# USB.net
KiCad netlist of a schematic drawn in Altium Designer
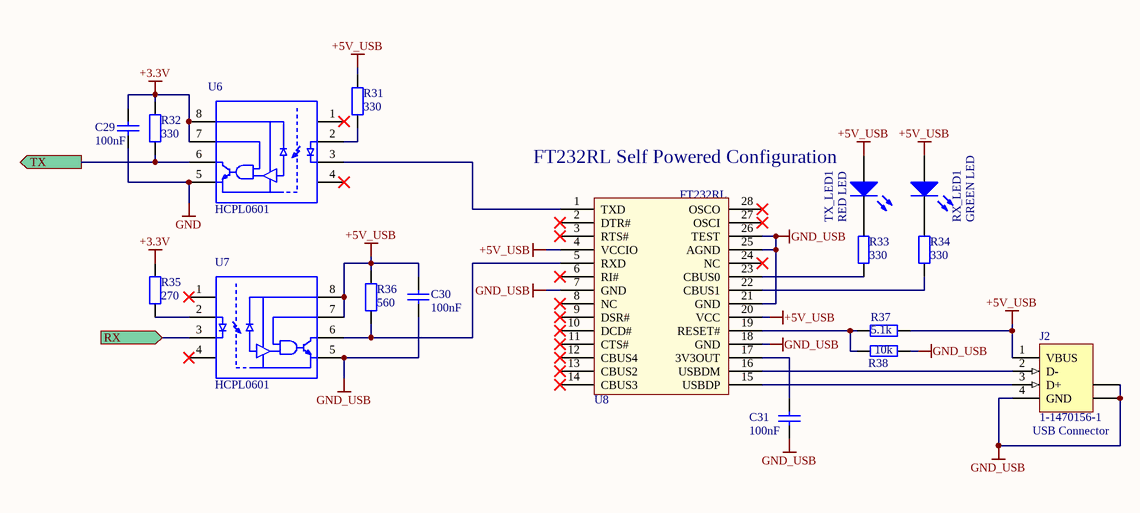
[diagram p0: USB.SchDoc]

(export (version "E")
  (design (tool "Eeschema 10.0.6"))
  (components
    (comp (ref "C29")
      (value "100nF")
      (footprint "1206_REFLOW")
      (fields (field (name "Comment") "Cap 1206"))
      (libsource (lib "Capacitors") (part "Cap 1206"))
    )
    (comp (ref "C30")
      (value "100nF")
      (footprint "1206_REFLOW")
      (fields (field (name "Comment") "Cap 1206"))
      (libsource (lib "Capacitors") (part "Cap 1206"))
    )
    (comp (ref "C31")
      (value "100nF")
      (footprint "3216[1206]")
      (fields (field (name "Comment") "Cap"))
      (libsource (lib "Capacitors") (part "Cap"))
    )
    (comp (ref "J2")
      (value "1-1470156-1")
      (footprint "USB2.5-2H4D")
      (description "USB 1.1, Right Angle, Thru-Hole, B Type, Receptacle, 4 Position, White")
      (fields (field (name "PUBLISHER") "Altium Limited"))
      (libsource (lib "AMP Serial Bus USB") (part "1-1470156-1"))
    )
    (comp (ref "R31")
      (value "330")
      (footprint "1206_REFLOW")
      (fields (field (name "Comment") "RES"))
      (libsource (lib "Resistor") (part "RES 1"))
    )
    (comp (ref "R32")
      (value "330")
      (footprint "1206_REFLOW")
      (fields (field (name "Comment") "RES"))
      (libsource (lib "Resistor") (part "RES 1"))
    )
    (comp (ref "R33")
      (value "330")
      (footprint "3216[1206]")
      (fields (field (name "Comment") "Resistor"))
      (libsource (lib "") (part "RES1_1"))
    )
    (comp (ref "R34")
      (value "330")
      (footprint "3216[1206]")
      (fields (field (name "Comment") "Resistor"))
      (libsource (lib "") (part "RES1_1"))
    )
    (comp (ref "R35")
      (value "270")
      (footprint "1206_REFLOW")
      (fields (field (name "Comment") "RES"))
      (libsource (lib "Resistor") (part "RES 1"))
    )
    (comp (ref "R36")
      (value "560")
      (footprint "1206_REFLOW")
      (fields (field (name "Comment") "RES"))
      (libsource (lib "Resistor") (part "RES 1"))
    )
    (comp (ref "R37")
      (value "5.1k")
      (footprint "3216[1206]")
      (fields (field (name "Comment") "Resistor"))
      (libsource (lib "Resistor") (part "RES1"))
    )
    (comp (ref "R38")
      (value "10k")
      (footprint "3216[1206]")
      (fields (field (name "Comment") "Resistor"))
      (libsource (lib "") (part "RES1_2"))
    )
    (comp (ref "RX_LED1") (value "GREEN LED") (footprint "LED_1206") (libsource (lib "LED") (part "LED")))
    (comp (ref "TX_LED1") (value "RED LED") (footprint "LED_1206") (libsource (lib "LED") (part "LED")))
    (comp (ref "U6")
      (value "HCPL0601")
      (footprint "SO8_HIS")
      (libsource (lib "Optocoupler") (part "HCPL0601"))
    )
    (comp (ref "U7")
      (value "HCPL0601")
      (footprint "SO8_HIS")
      (libsource (lib "Optocoupler") (part "HCPL0601"))
    )
    (comp (ref "U8") (value "FT232RL") (footprint "SSOP28") (libsource (lib "COMM") (part "FT232RL")))
  )
  (nets
    (net (code "1") (name "+3.3V") (class "Default")
      (node (ref "C29") (pin "1") (pinfunction "1_1") (pintype "passive"))
      (node (ref "R32") (pin "1") (pinfunction "1_1") (pintype "passive"))
      (node (ref "R35") (pin "1") (pinfunction "1_1") (pintype "passive"))
      (node (ref "U6") (pin "7") (pinfunction "Ve_7") (pintype "passive"))
      (node (ref "U6") (pin "8") (pinfunction "Vcc_8") (pintype "passive"))
    )
    (net (code "2") (name "+5V_USB") (class "Default")
      (node (ref "C30") (pin "1") (pinfunction "1_1") (pintype "passive"))
      (node (ref "J2") (pin "1") (pinfunction "VBUS_1") (pintype "power_in"))
      (node (ref "R31") (pin "1") (pinfunction "1_1") (pintype "passive"))
      (node (ref "R36") (pin "1") (pinfunction "1_1") (pintype "passive"))
      (node (ref "R37") (pin "2") (pinfunction "2_2") (pintype "passive"))
      (node (ref "RX_LED1") (pin "A") (pinfunction "A_A") (pintype "passive"))
      (node (ref "TX_LED1") (pin "A") (pinfunction "A_A") (pintype "passive"))
      (node (ref "U7") (pin "7") (pinfunction "Ve_7") (pintype "passive"))
      (node (ref "U7") (pin "8") (pinfunction "Vcc_8") (pintype "passive"))
      (node (ref "U8") (pin "20") (pinfunction "VCC_20") (pintype "passive"))
      (node (ref "U8") (pin "4") (pinfunction "VCCIO_4") (pintype "passive"))
    )
    (net (code "3") (name "/RX") (class "Default")
      (node (ref "U7") (pin "3") (pinfunction "Vf-_3") (pintype "passive"))
    )
    (net (code "4") (name "/TX") (class "Default")
      (node (ref "R32") (pin "2") (pinfunction "2_2") (pintype "passive"))
      (node (ref "U6") (pin "6") (pinfunction "Vo_6") (pintype "passive"))
    )
    (net (code "5") (name "GND") (class "Default")
      (node (ref "C29") (pin "2") (pinfunction "2_2") (pintype "passive"))
      (node (ref "U6") (pin "5") (pinfunction "GND_5") (pintype "passive"))
    )
    (net (code "6") (name "GND_USB") (class "Default")
      (node (ref "C30") (pin "2") (pinfunction "2_2") (pintype "passive"))
      (node (ref "C31") (pin "1") (pinfunction "1_1") (pintype "passive"))
      (node (ref "J2") (pin "4") (pinfunction "GND_4") (pintype "power_in"))
      (node (ref "J2") (pin "5") (pinfunction "SHLD_5") (pintype "passive"))
      (node (ref "J2") (pin "6") (pinfunction "SHLD_6") (pintype "passive"))
      (node (ref "R38") (pin "1") (pinfunction "1_1") (pintype "passive"))
      (node (ref "U7") (pin "5") (pinfunction "GND_5") (pintype "passive"))
      (node (ref "U8") (pin "18") (pinfunction "GND_18") (pintype "passive"))
      (node (ref "U8") (pin "21") (pinfunction "GND_21") (pintype "passive"))
      (node (ref "U8") (pin "25") (pinfunction "AGND_25") (pintype "passive"))
      (node (ref "U8") (pin "26") (pinfunction "TEST_26") (pintype "passive"))
      (node (ref "U8") (pin "7") (pinfunction "GND_7") (pintype "passive"))
    )
    (net (code "7") (name "Net-(J2-D+)") (class "Default")
      (node (ref "J2") (pin "3") (pinfunction "D+_3") (pintype "input"))
      (node (ref "U8") (pin "15") (pinfunction "USBDP_15") (pintype "passive"))
    )
    (net (code "8") (name "Net-(J2-D-)") (class "Default")
      (node (ref "J2") (pin "2") (pinfunction "D-_2") (pintype "input"))
      (node (ref "U8") (pin "16") (pinfunction "USBDM_16") (pintype "passive"))
    )
    (net (code "9") (name "Net-(R33-Pad2)") (class "Default")
      (node (ref "R33") (pin "2") (pinfunction "2_2") (pintype "passive"))
      (node (ref "TX_LED1") (pin "K") (pinfunction "K_K") (pintype "passive"))
    )
    (net (code "10") (name "Net-(R34-Pad2)") (class "Default")
      (node (ref "R34") (pin "2") (pinfunction "2_2") (pintype "passive"))
      (node (ref "RX_LED1") (pin "K") (pinfunction "K_K") (pintype "passive"))
    )
    (net (code "11") (name "Net-(U6-Vf+)") (class "Default")
      (node (ref "R31") (pin "2") (pinfunction "2_2") (pintype "passive"))
      (node (ref "U6") (pin "2") (pinfunction "Vf+_2") (pintype "passive"))
    )
    (net (code "12") (name "Net-(U6-Vf-)") (class "Default")
      (node (ref "U6") (pin "3") (pinfunction "Vf-_3") (pintype "passive"))
      (node (ref "U8") (pin "1") (pinfunction "TXD_1") (pintype "passive"))
    )
    (net (code "13") (name "Net-(U7-Vf+)") (class "Default")
      (node (ref "R35") (pin "2") (pinfunction "2_2") (pintype "passive"))
      (node (ref "U7") (pin "2") (pinfunction "Vf+_2") (pintype "passive"))
    )
    (net (code "14") (name "Net-(U7-Vo)") (class "Default")
      (node (ref "R36") (pin "2") (pinfunction "2_2") (pintype "passive"))
      (node (ref "U7") (pin "6") (pinfunction "Vo_6") (pintype "passive"))
      (node (ref "U8") (pin "5") (pinfunction "RXD_5") (pintype "passive"))
    )
    (net (code "15") (name "Net-(U8-3V3OUT)") (class "Default")
      (node (ref "C31") (pin "2") (pinfunction "2_2") (pintype "passive"))
      (node (ref "U8") (pin "17") (pinfunction "3V3OUT_17") (pintype "passive"))
    )
    (net (code "16") (name "Net-(U8-CBUS0)") (class "Default")
      (node (ref "R33") (pin "1") (pinfunction "1_1") (pintype "passive"))
      (node (ref "U8") (pin "23") (pinfunction "CBUS0_23") (pintype "passive"))
    )
    (net (code "17") (name "Net-(U8-CBUS1)") (class "Default")
      (node (ref "R34") (pin "1") (pinfunction "1_1") (pintype "passive"))
      (node (ref "U8") (pin "22") (pinfunction "CBUS1_22") (pintype "passive"))
    )
    (net (code "18") (name "Net-(U8-RESET#)") (class "Default")
      (node (ref "R37") (pin "1") (pinfunction "1_1") (pintype "passive"))
      (node (ref "R38") (pin "2") (pinfunction "2_2") (pintype "passive"))
      (node (ref "U8") (pin "19") (pinfunction "RESET#_19") (pintype "passive"))
    )
    (net (code "19") (name "unconnected-(U6-N{slash}C-Pad1)") (class "Default")
      (node (ref "U6") (pin "1") (pinfunction "N/C_1") (pintype "passive+no_connect"))
    )
    (net (code "20") (name "unconnected-(U6-N{slash}C-Pad4)") (class "Default")
      (node (ref "U6") (pin "4") (pinfunction "N/C_4") (pintype "passive+no_connect"))
    )
    (net (code "21") (name "unconnected-(U7-N{slash}C-Pad1)") (class "Default")
      (node (ref "U7") (pin "1") (pinfunction "N/C_1") (pintype "passive+no_connect"))
    )
    (net (code "22") (name "unconnected-(U7-N{slash}C-Pad4)") (class "Default")
      (node (ref "U7") (pin "4") (pinfunction "N/C_4") (pintype "passive+no_connect"))
    )
    (net (code "23") (name "unconnected-(U8-CBUS2-Pad13)") (class "Default")
      (node (ref "U8") (pin "13") (pinfunction "CBUS2_13") (pintype "passive+no_connect"))
    )
    (net (code "24") (name "unconnected-(U8-CBUS3-Pad14)") (class "Default")
      (node (ref "U8") (pin "14") (pinfunction "CBUS3_14") (pintype "passive+no_connect"))
    )
    (net (code "25") (name "unconnected-(U8-CBUS4-Pad12)") (class "Default")
      (node (ref "U8") (pin "12") (pinfunction "CBUS4_12") (pintype "passive+no_connect"))
    )
    (net (code "26") (name "unconnected-(U8-CTS#-Pad11)") (class "Default")
      (node (ref "U8") (pin "11") (pinfunction "CTS#_11") (pintype "passive+no_connect"))
    )
    (net (code "27") (name "unconnected-(U8-DCD#-Pad10)") (class "Default")
      (node (ref "U8") (pin "10") (pinfunction "DCD#_10") (pintype "passive+no_connect"))
    )
    (net (code "28") (name "unconnected-(U8-DSR#-Pad9)") (class "Default")
      (node (ref "U8") (pin "9") (pinfunction "DSR#_9") (pintype "passive+no_connect"))
    )
    (net (code "29") (name "unconnected-(U8-DTR#-Pad2)") (class "Default")
      (node (ref "U8") (pin "2") (pinfunction "DTR#_2") (pintype "passive+no_connect"))
    )
    (net (code "30") (name "unconnected-(U8-NC-Pad8)") (class "Default")
      (node (ref "U8") (pin "8") (pinfunction "NC_8") (pintype "passive+no_connect"))
    )
    (net (code "31") (name "unconnected-(U8-NC-Pad24)") (class "Default")
      (node (ref "U8") (pin "24") (pinfunction "NC_24") (pintype "passive+no_connect"))
    )
    (net (code "32") (name "unconnected-(U8-OSCI-Pad27)") (class "Default")
      (node (ref "U8") (pin "27") (pinfunction "OSCI_27") (pintype "passive+no_connect"))
    )
    (net (code "33") (name "unconnected-(U8-OSCO-Pad28)") (class "Default")
      (node (ref "U8") (pin "28") (pinfunction "OSCO_28") (pintype "passive+no_connect"))
    )
    (net (code "34") (name "unconnected-(U8-RI#-Pad6)") (class "Default")
      (node (ref "U8") (pin "6") (pinfunction "RI#_6") (pintype "passive+no_connect"))
    )
    (net (code "35") (name "unconnected-(U8-RTS#-Pad3)") (class "Default")
      (node (ref "U8") (pin "3") (pinfunction "RTS#_3") (pintype "passive+no_connect"))
    )
  )
)
